# LTR-329ALS-01-Breakout_v10.net
KiCad netlist of a schematic drawn in EAGLE
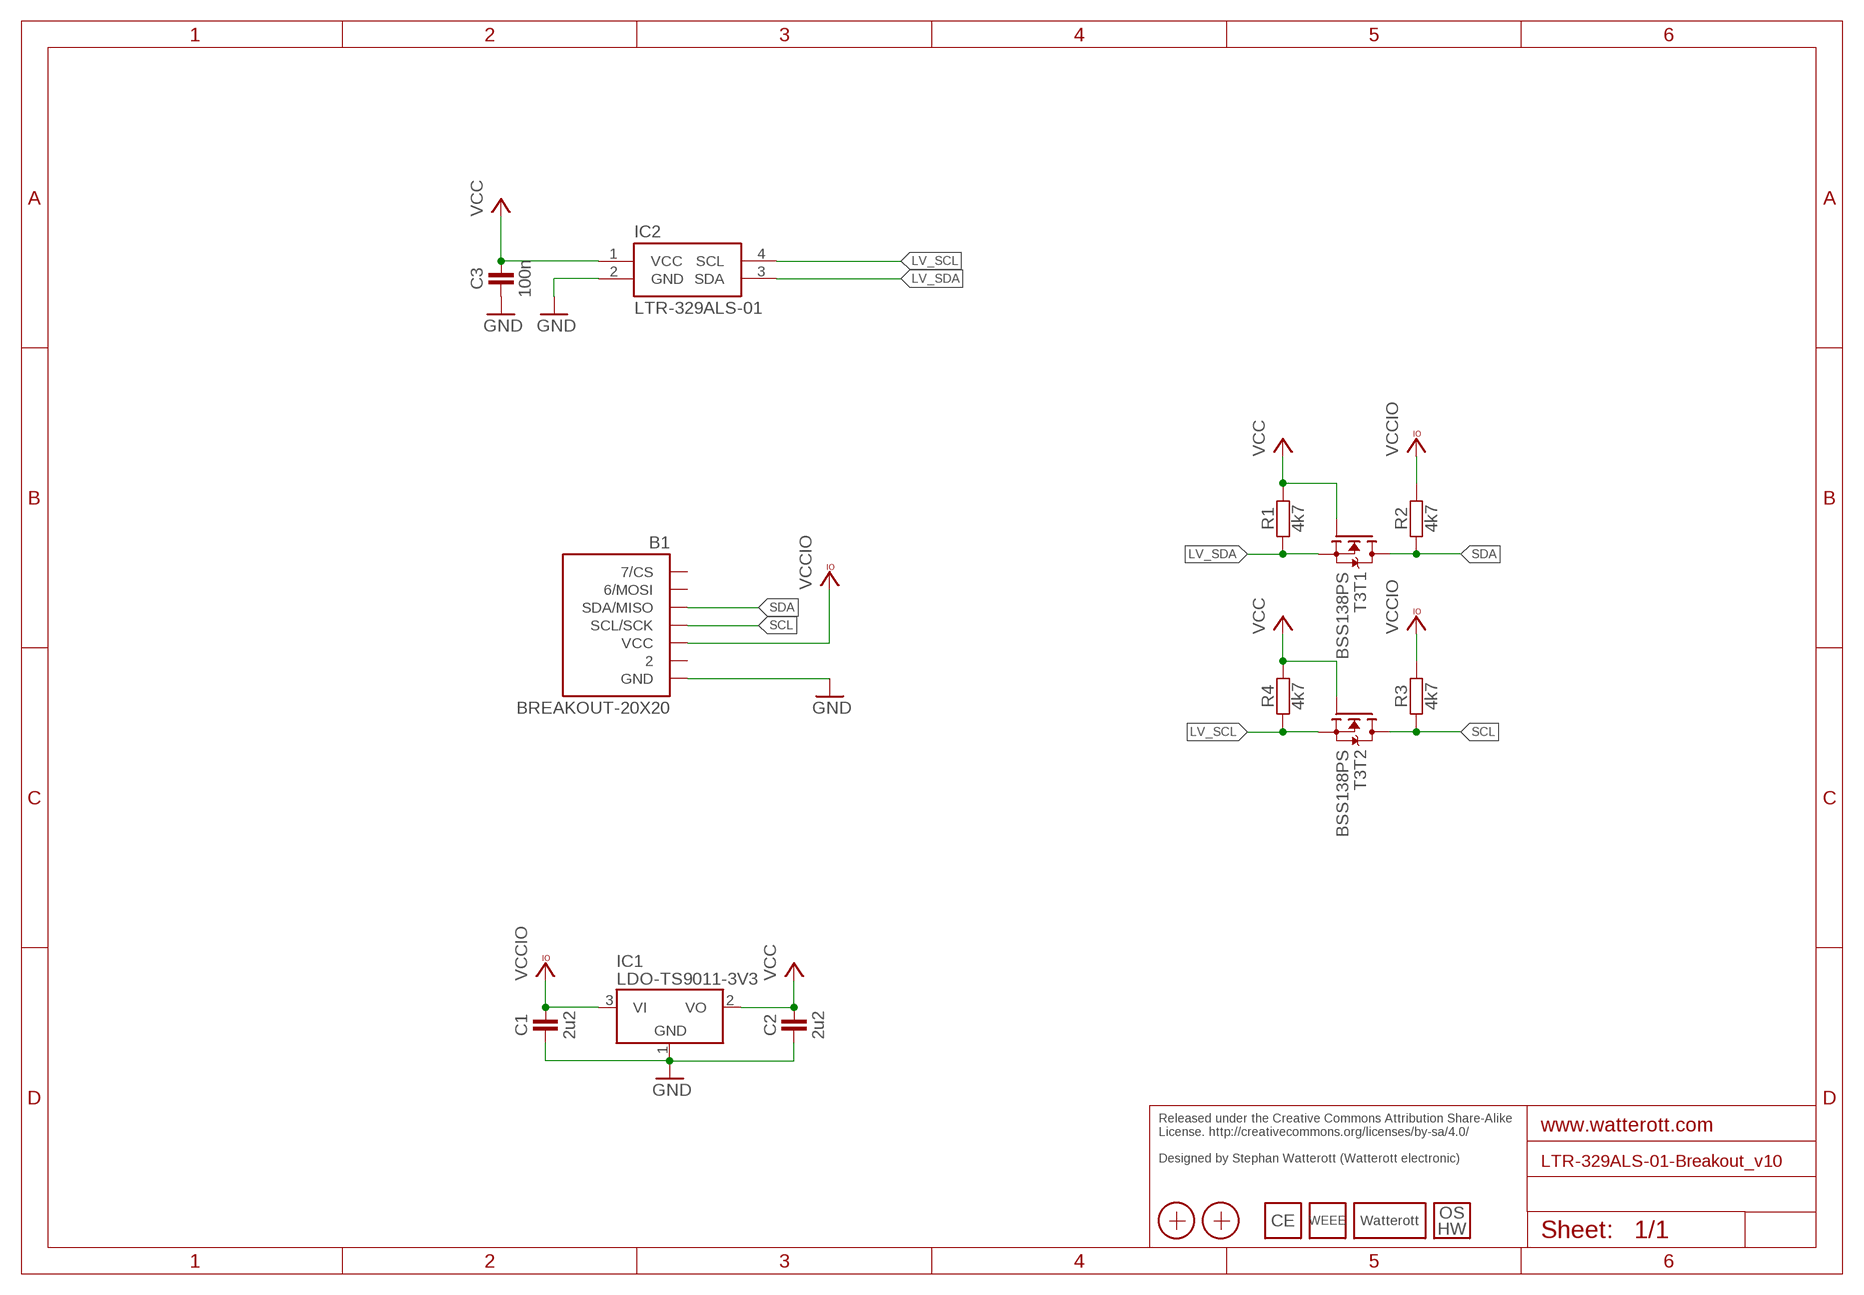
[diagram p0: schematic, sheet 1]

(export (version "E")
  (design (tool "Eeschema 10.0.6"))
  (components
    (comp (ref "B1")
      (value "BREAKOUT-20X20")
      (footprint "eagle-import:BREAKOUT-20X20")
      (libsource (lib "eagle-import") (part "BREAKOUT-20X20"))
    )
    (comp (ref "C1")
      (value "2u2")
      (footprint "eagle-import:C0402")
      (libsource (lib "eagle-import") (part "CAPACITOR-0402"))
    )
    (comp (ref "C2")
      (value "2u2")
      (footprint "eagle-import:C0402")
      (libsource (lib "eagle-import") (part "CAPACITOR-0402"))
    )
    (comp (ref "C3")
      (value "100n")
      (footprint "eagle-import:C0402")
      (libsource (lib "eagle-import") (part "CAPACITOR-0402"))
    )
    (comp (ref "IC1")
      (value "LDO-TS9011-3V3")
      (footprint "eagle-import:SOT23")
      (libsource (lib "eagle-import") (part "LDO-TS9011-3V3"))
    )
    (comp (ref "IC2")
      (value "LTR-329ALS-01")
      (footprint "eagle-import:LTR-329ALS-01")
      (libsource (lib "eagle-import") (part "LTR-329ALS-01"))
    )
    (comp (ref "LOGO3")
      (value "LOGO_WEEE-4")
      (footprint "eagle-import:WEEE_4MM")
      (libsource (lib "eagle-import") (part "LOGO_WEEE-4"))
    )
    (comp (ref "LOGO4")
      (value "LOGO_CE-4")
      (footprint "eagle-import:CE_4MM")
      (libsource (lib "eagle-import") (part "LOGO_CE-4"))
    )
    (comp (ref "LOGO5")
      (value "LOGO_SPARK-4")
      (footprint "eagle-import:SPARK_4MM")
      (libsource (lib "eagle-import") (part "LOGO_SPARK-4"))
    )
    (comp (ref "LOGO6")
      (value "LOGO_OSHW-2")
      (footprint "eagle-import:OSHW_2MM")
      (libsource (lib "eagle-import") (part "LOGO_OSHW-2"))
    )
    (comp (ref "R1")
      (value "4k7")
      (footprint "eagle-import:C0402")
      (libsource (lib "eagle-import") (part "RESISTOR-0402"))
    )
    (comp (ref "R2")
      (value "4k7")
      (footprint "eagle-import:C0402")
      (libsource (lib "eagle-import") (part "RESISTOR-0402"))
    )
    (comp (ref "R3")
      (value "4k7")
      (footprint "eagle-import:C0402")
      (libsource (lib "eagle-import") (part "RESISTOR-0402"))
    )
    (comp (ref "R4")
      (value "4k7")
      (footprint "eagle-import:C0402")
      (libsource (lib "eagle-import") (part "RESISTOR-0402"))
    )
    (comp (ref "T3")
      (value "BSS138PS")
      (footprint "eagle-import:SOT363")
      (libsource (lib "eagle-import") (part "BSS138PS"))
    )
    (comp (ref "X1")
      (value "PASSER-07")
      (footprint "eagle-import:PASSER_07MM")
      (libsource (lib "eagle-import") (part "PASSER-07"))
    )
    (comp (ref "X2")
      (value "PASSER-07")
      (footprint "eagle-import:PASSER_07MM")
      (libsource (lib "eagle-import") (part "PASSER-07"))
    )
  )
  (nets
    (net (code "1") (name "GND") (class "Default")
      (node (ref "B1") (pin "GND") (pinfunction "GND_GND") (pintype "power_in"))
      (node (ref "C1") (pin "1") (pinfunction "1_1") (pintype "passive"))
      (node (ref "C2") (pin "1") (pinfunction "1_1") (pintype "passive"))
      (node (ref "C3") (pin "1") (pinfunction "1_1") (pintype "passive"))
      (node (ref "IC1") (pin "1") (pinfunction "GND_1") (pintype "passive"))
      (node (ref "IC2") (pin "2") (pinfunction "GND_2") (pintype "power_in"))
    )
    (net (code "2") (name "LV_SCL") (class "Default")
      (node (ref "IC2") (pin "4") (pinfunction "SCL_4") (pintype "bidirectional"))
      (node (ref "R4") (pin "1") (pinfunction "1_1") (pintype "passive"))
      (node (ref "T3") (pin "4") (pinfunction "S_4") (pintype "passive"))
    )
    (net (code "3") (name "LV_SDA") (class "Default")
      (node (ref "IC2") (pin "3") (pinfunction "SDA_3") (pintype "bidirectional"))
      (node (ref "R1") (pin "1") (pinfunction "1_1") (pintype "passive"))
      (node (ref "T3") (pin "1") (pinfunction "S_1") (pintype "passive"))
    )
    (net (code "4") (name "SCL") (class "Default")
      (node (ref "B1") (pin "SCL/SCK") (pinfunction "SCL/SCK_SCL/SCK") (pintype "bidirectional"))
      (node (ref "R3") (pin "1") (pinfunction "1_1") (pintype "passive"))
      (node (ref "T3") (pin "3") (pinfunction "D_3") (pintype "passive"))
    )
    (net (code "5") (name "SDA") (class "Default")
      (node (ref "B1") (pin "SDA/MISO") (pinfunction "SDA/MISO_SDA/MISO") (pintype "bidirectional"))
      (node (ref "R2") (pin "1") (pinfunction "1_1") (pintype "passive"))
      (node (ref "T3") (pin "6") (pinfunction "D_6") (pintype "passive"))
    )
    (net (code "6") (name "VCC") (class "Default")
      (node (ref "C2") (pin "2") (pinfunction "2_2") (pintype "passive"))
      (node (ref "C3") (pin "2") (pinfunction "2_2") (pintype "passive"))
      (node (ref "IC1") (pin "2") (pinfunction "VO_2") (pintype "passive"))
      (node (ref "IC2") (pin "1") (pinfunction "VCC_1") (pintype "power_in"))
      (node (ref "R1") (pin "2") (pinfunction "2_2") (pintype "passive"))
      (node (ref "R4") (pin "2") (pinfunction "2_2") (pintype "passive"))
      (node (ref "T3") (pin "2") (pinfunction "G_2") (pintype "passive"))
      (node (ref "T3") (pin "5") (pinfunction "G_5") (pintype "passive"))
    )
    (net (code "7") (name "VCCIO") (class "Default")
      (node (ref "B1") (pin "VCC") (pinfunction "VCC_VCC") (pintype "power_in"))
      (node (ref "C1") (pin "2") (pinfunction "2_2") (pintype "passive"))
      (node (ref "IC1") (pin "3") (pinfunction "VI_3") (pintype "input"))
      (node (ref "R2") (pin "2") (pinfunction "2_2") (pintype "passive"))
      (node (ref "R3") (pin "2") (pinfunction "2_2") (pintype "passive"))
    )
    (net (code "8") (name "unconnected-(B1-6{slash}MOSI-PadMOSI)") (class "Default")
      (node (ref "B1") (pin "MOSI") (pinfunction "6/MOSI_MOSI") (pintype "bidirectional"))
    )
    (net (code "9") (name "unconnected-(B1-7{slash}CS-PadCS)") (class "Default")
      (node (ref "B1") (pin "CS") (pinfunction "7/CS_CS") (pintype "bidirectional"))
    )
    (net (code "10") (name "unconnected-(B1-Pad2)") (class "Default")
      (node (ref "B1") (pin "2") (pinfunction "2_2") (pintype "bidirectional"))
    )
  )
)
